# Torch-Led_board.net
KiCad netlist of a schematic drawn in EAGLE
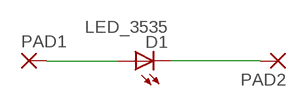
[diagram p0: schematic, sheet 1]

(export (version "E")
  (design (tool "Eeschema 10.0.6"))
  (components
    (comp (ref "D1")
      (value "LED_3535")
      (footprint "eagle-import:LED3535")
      (libsource (lib "eagle-import") (part "LED_3535"))
    )
    (comp (ref "PAD1")
      (value "2,15/1,0")
      (footprint "eagle-import:2,15_1,0")
      (libsource (lib "eagle-import") (part "2,15/1,0"))
    )
    (comp (ref "PAD2")
      (value "2,15/1,0")
      (footprint "eagle-import:2,15_1,0")
      (libsource (lib "eagle-import") (part "2,15/1,0"))
    )
  )
  (nets
    (net (code "1") (name "Net-(D1-A)") (class "Default")
      (node (ref "D1") (pin "P$1") (pinfunction "A_P$1") (pintype "passive"))
      (node (ref "PAD1") (pin "1") (pinfunction "P_1") (pintype "passive"))
    )
    (net (code "2") (name "Net-(D1-C)") (class "Default")
      (node (ref "D1") (pin "P$3") (pinfunction "C_P$3") (pintype "passive"))
      (node (ref "PAD2") (pin "1") (pinfunction "P_1") (pintype "passive"))
    )
  )
)
